# RSS_0_4.net
KiCad netlist of a schematic drawn in EAGLE
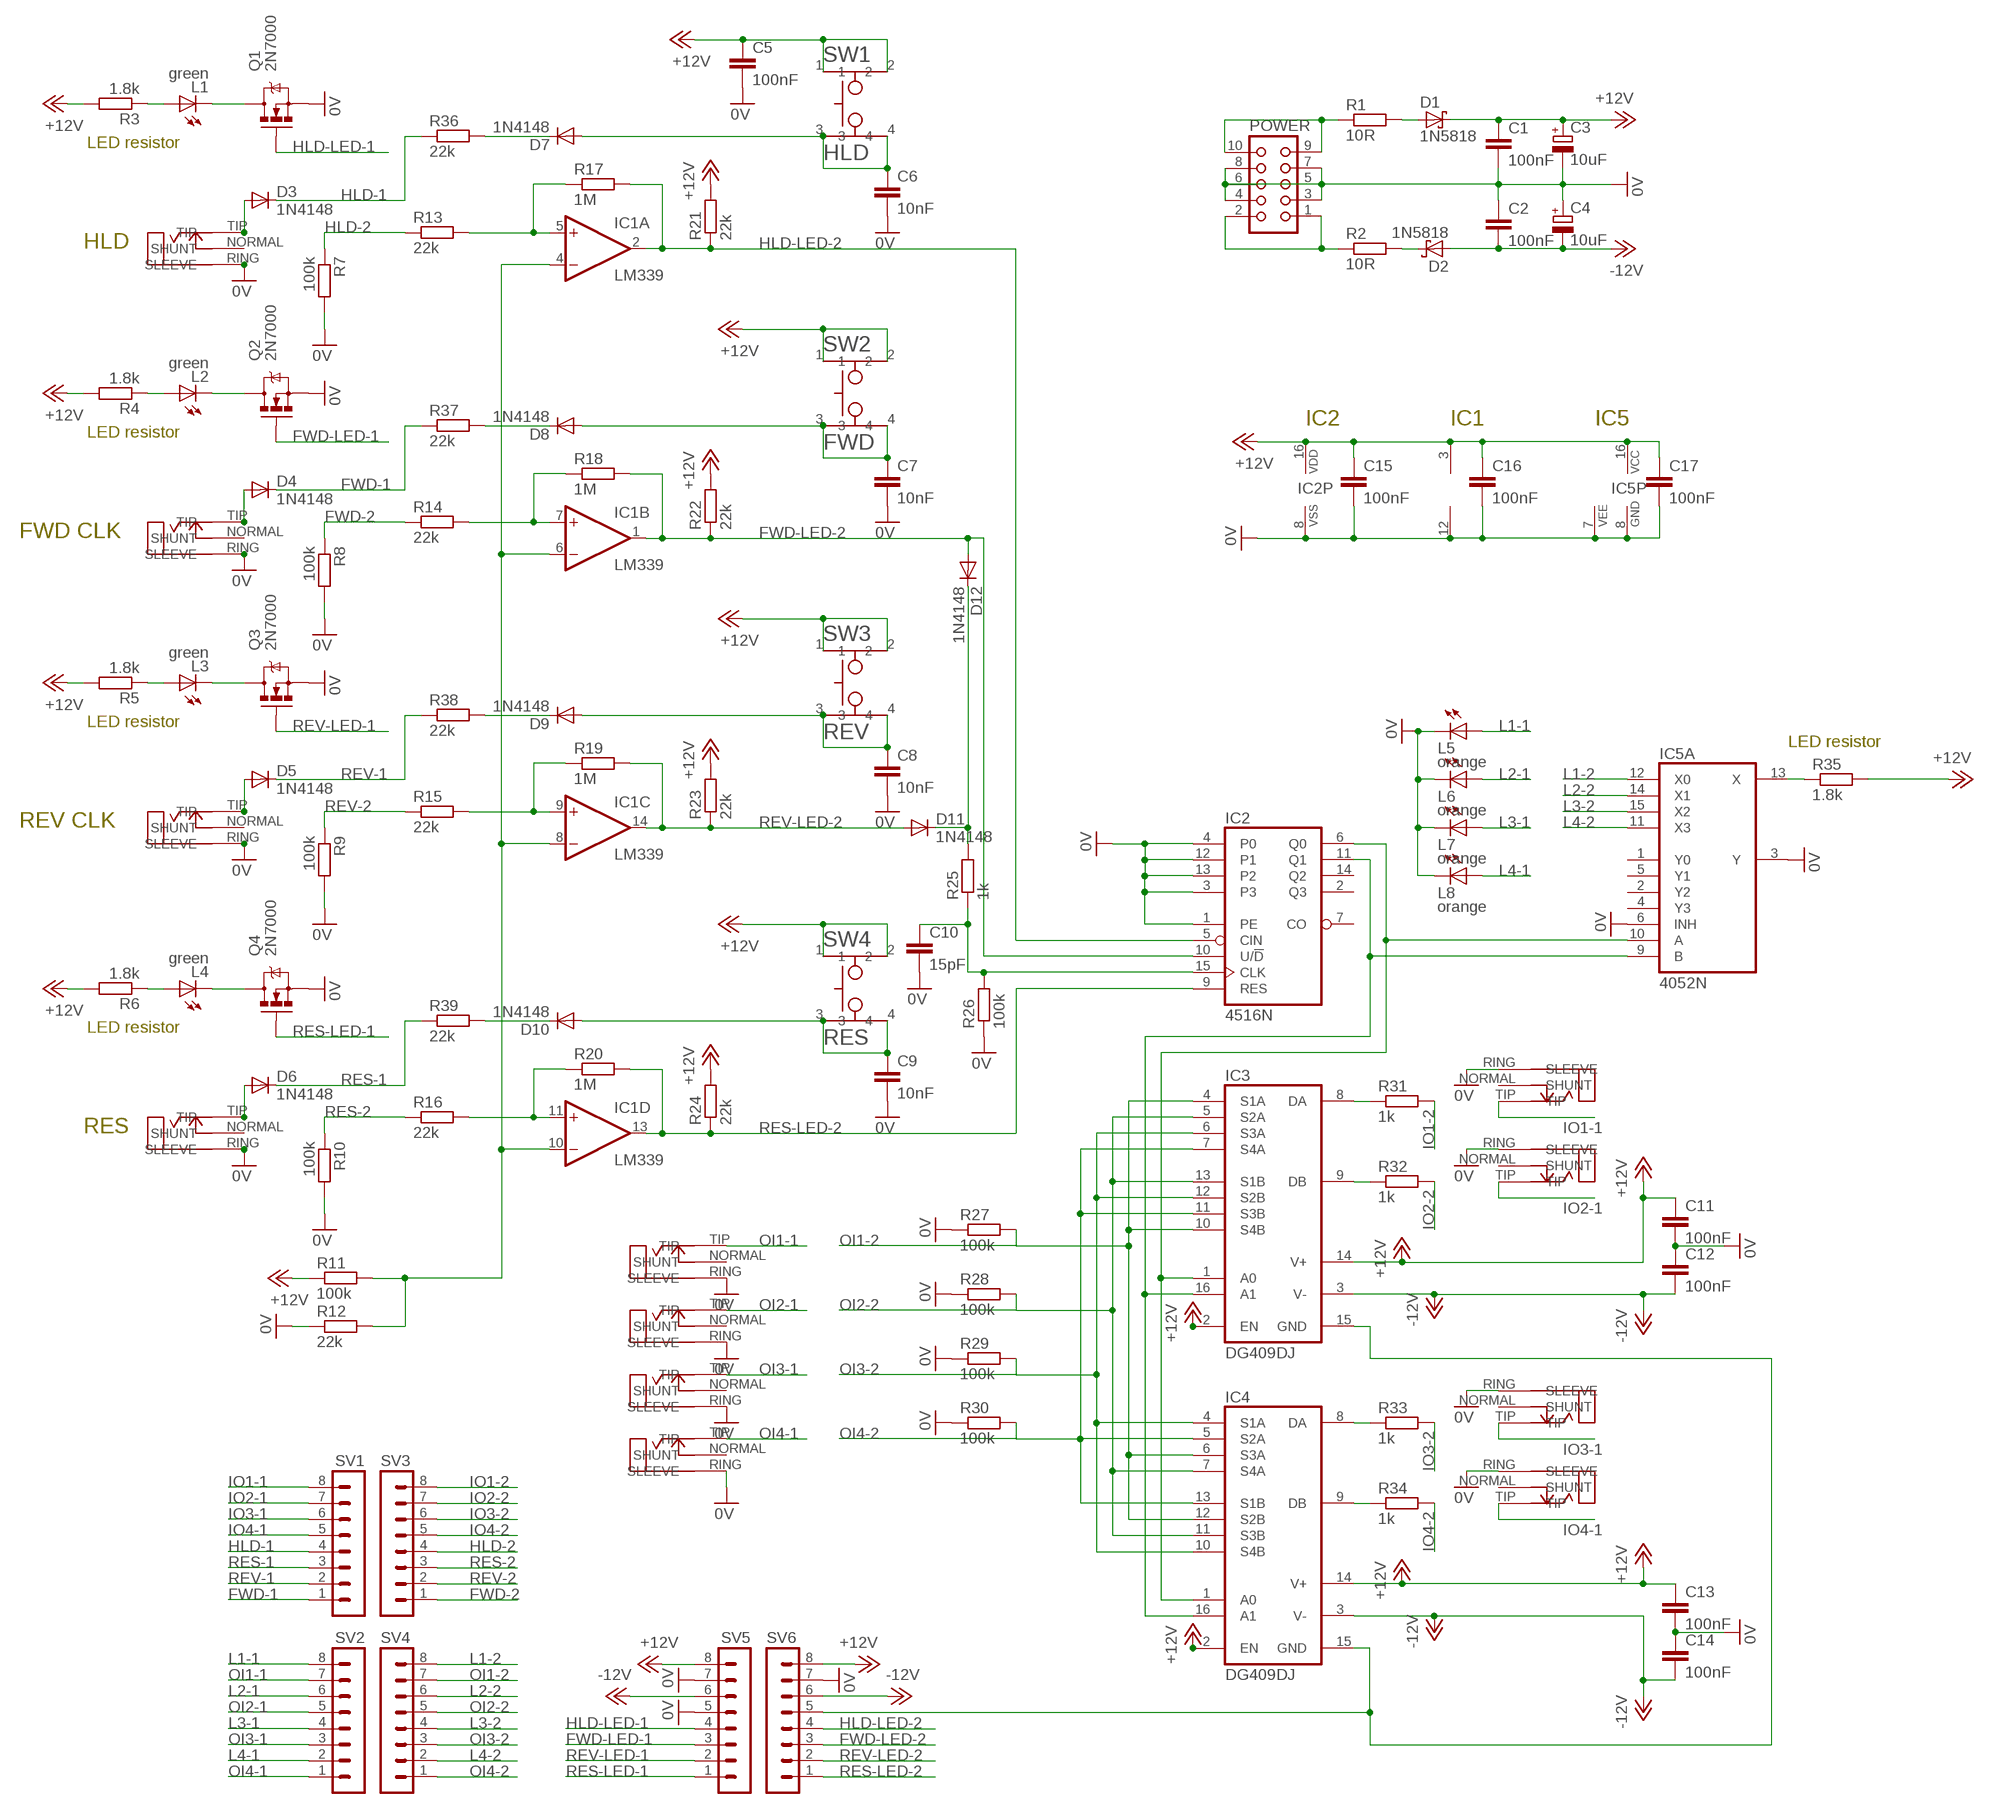
[diagram p0: schematic, sheet 1]

(export (version "E")
  (design (tool "Eeschema 10.0.6"))
  (components
    (comp (ref "C1")
      (value "100nF")
      (footprint "eagle-import:C025-024X044")
      (libsource (lib "eagle-import") (part "C-EU025-024X044"))
    )
    (comp (ref "C2")
      (value "100nF")
      (footprint "eagle-import:C025-024X044")
      (libsource (lib "eagle-import") (part "C-EU025-024X044"))
    )
    (comp (ref "C3")
      (value "10uF")
      (footprint "eagle-import:E2-5")
      (libsource (lib "eagle-import") (part "CPOL-EUE2-5"))
    )
    (comp (ref "C4")
      (value "10uF")
      (footprint "eagle-import:E2-5")
      (libsource (lib "eagle-import") (part "CPOL-EUE2-5"))
    )
    (comp (ref "C5")
      (value "100nF")
      (footprint "eagle-import:C025-024X044")
      (libsource (lib "eagle-import") (part "C-EU025-024X044"))
    )
    (comp (ref "C6")
      (value "10nF")
      (footprint "eagle-import:C025-024X044")
      (libsource (lib "eagle-import") (part "C-EU025-024X044"))
    )
    (comp (ref "C7")
      (value "10nF")
      (footprint "eagle-import:C025-024X044")
      (libsource (lib "eagle-import") (part "C-EU025-024X044"))
    )
    (comp (ref "C8")
      (value "10nF")
      (footprint "eagle-import:C025-024X044")
      (libsource (lib "eagle-import") (part "C-EU025-024X044"))
    )
    (comp (ref "C9")
      (value "10nF")
      (footprint "eagle-import:C025-024X044")
      (libsource (lib "eagle-import") (part "C-EU025-024X044"))
    )
    (comp (ref "C10")
      (value "15pF")
      (footprint "eagle-import:C025-024X044")
      (libsource (lib "eagle-import") (part "C-EU025-024X044"))
    )
    (comp (ref "C11")
      (value "100nF")
      (footprint "eagle-import:C025-024X044")
      (libsource (lib "eagle-import") (part "C-EU025-024X044"))
    )
    (comp (ref "C12")
      (value "100nF")
      (footprint "eagle-import:C025-024X044")
      (libsource (lib "eagle-import") (part "C-EU025-024X044"))
    )
    (comp (ref "C13")
      (value "100nF")
      (footprint "eagle-import:C025-024X044")
      (libsource (lib "eagle-import") (part "C-EU025-024X044"))
    )
    (comp (ref "C14")
      (value "100nF")
      (footprint "eagle-import:C025-024X044")
      (libsource (lib "eagle-import") (part "C-EU025-024X044"))
    )
    (comp (ref "C15")
      (value "100nF")
      (footprint "eagle-import:C025-024X044")
      (libsource (lib "eagle-import") (part "C-EU025-024X044"))
    )
    (comp (ref "C16")
      (value "100nF")
      (footprint "eagle-import:C025-024X044")
      (libsource (lib "eagle-import") (part "C-EU025-024X044"))
    )
    (comp (ref "C17")
      (value "100nF")
      (footprint "eagle-import:C025-024X044")
      (libsource (lib "eagle-import") (part "C-EU025-024X044"))
    )
    (comp (ref "D1")
      (value "1N5818")
      (footprint "eagle-import:DO41-7")
      (libsource (lib "eagle-import") (part "SB130DO-204AL"))
    )
    (comp (ref "D2")
      (value "1N5818")
      (footprint "eagle-import:DO41-7")
      (libsource (lib "eagle-import") (part "SB130DO-204AL"))
    )
    (comp (ref "D3")
      (value "1N4148")
      (footprint "eagle-import:DO35-7")
      (libsource (lib "eagle-import") (part "1N4148DO35-7"))
    )
    (comp (ref "D4")
      (value "1N4148")
      (footprint "eagle-import:DO35-7")
      (libsource (lib "eagle-import") (part "1N4148DO35-7"))
    )
    (comp (ref "D5")
      (value "1N4148")
      (footprint "eagle-import:DO35-7")
      (libsource (lib "eagle-import") (part "1N4148DO35-7"))
    )
    (comp (ref "D6")
      (value "1N4148")
      (footprint "eagle-import:DO35-7")
      (libsource (lib "eagle-import") (part "1N4148DO35-7"))
    )
    (comp (ref "D7")
      (value "1N4148")
      (footprint "eagle-import:DO35-7")
      (libsource (lib "eagle-import") (part "1N4148DO35-7"))
    )
    (comp (ref "D8")
      (value "1N4148")
      (footprint "eagle-import:DO35-7")
      (libsource (lib "eagle-import") (part "1N4148DO35-7"))
    )
    (comp (ref "D9")
      (value "1N4148")
      (footprint "eagle-import:DO35-7")
      (libsource (lib "eagle-import") (part "1N4148DO35-7"))
    )
    (comp (ref "D10")
      (value "1N4148")
      (footprint "eagle-import:DO35-7")
      (libsource (lib "eagle-import") (part "1N4148DO35-7"))
    )
    (comp (ref "D11")
      (value "1N4148")
      (footprint "eagle-import:DO35-7")
      (libsource (lib "eagle-import") (part "1N4148DO35-7"))
    )
    (comp (ref "D12")
      (value "1N4148")
      (footprint "eagle-import:DO35-7")
      (libsource (lib "eagle-import") (part "1N4148DO35-7"))
    )
    (comp (ref "FWD")
      (value "ERTHENVAR_3.5MM_JACK")
      (footprint "eagle-import:THONKICON")
      (libsource (lib "eagle-import") (part "ERTHENVAR_3.5MM_JACK"))
    )
    (comp (ref "HLD")
      (value "ERTHENVAR_3.5MM_JACK")
      (footprint "eagle-import:THONKICON")
      (libsource (lib "eagle-import") (part "ERTHENVAR_3.5MM_JACK"))
    )
    (comp (ref "I/O1")
      (value "ERTHENVAR_3.5MM_JACK")
      (footprint "eagle-import:THONKICON")
      (libsource (lib "eagle-import") (part "ERTHENVAR_3.5MM_JACK"))
    )
    (comp (ref "I/O2")
      (value "ERTHENVAR_3.5MM_JACK")
      (footprint "eagle-import:THONKICON")
      (libsource (lib "eagle-import") (part "ERTHENVAR_3.5MM_JACK"))
    )
    (comp (ref "I/O3")
      (value "ERTHENVAR_3.5MM_JACK")
      (footprint "eagle-import:THONKICON")
      (libsource (lib "eagle-import") (part "ERTHENVAR_3.5MM_JACK"))
    )
    (comp (ref "I/O4")
      (value "ERTHENVAR_3.5MM_JACK")
      (footprint "eagle-import:THONKICON")
      (libsource (lib "eagle-import") (part "ERTHENVAR_3.5MM_JACK"))
    )
    (comp (ref "IC1")
      (value "LM339")
      (footprint "eagle-import:DIL14")
      (libsource (lib "eagle-import") (part "LM2901N"))
    )
    (comp (ref "IC2")
      (value "4516N")
      (footprint "eagle-import:DIL16")
      (libsource (lib "eagle-import") (part "4516N"))
    )
    (comp (ref "IC3")
      (value "DG409DJ")
      (footprint "eagle-import:DIL16")
      (fields (field (name "MF") "INTERSIL"))
      (libsource (lib "eagle-import") (part "DG409DJ"))
    )
    (comp (ref "IC4")
      (value "DG409DJ")
      (footprint "eagle-import:DIL16")
      (fields (field (name "MF") "INTERSIL"))
      (libsource (lib "eagle-import") (part "DG409DJ"))
    )
    (comp (ref "IC5")
      (value "4052N")
      (footprint "eagle-import:DIL16")
      (libsource (lib "eagle-import") (part "4052N"))
    )
    (comp (ref "L1")
      (value "green")
      (footprint "eagle-import:LED3MM")
      (libsource (lib "eagle-import") (part "LED3MM"))
    )
    (comp (ref "L2")
      (value "green")
      (footprint "eagle-import:LED3MM")
      (libsource (lib "eagle-import") (part "LED3MM"))
    )
    (comp (ref "L3")
      (value "green")
      (footprint "eagle-import:LED3MM")
      (libsource (lib "eagle-import") (part "LED3MM"))
    )
    (comp (ref "L4")
      (value "green")
      (footprint "eagle-import:LED3MM")
      (libsource (lib "eagle-import") (part "LED3MM"))
    )
    (comp (ref "L5")
      (value "orange")
      (footprint "eagle-import:LED3MM")
      (libsource (lib "eagle-import") (part "LED3MM"))
    )
    (comp (ref "L6")
      (value "orange")
      (footprint "eagle-import:LED3MM")
      (libsource (lib "eagle-import") (part "LED3MM"))
    )
    (comp (ref "L7")
      (value "orange")
      (footprint "eagle-import:LED3MM")
      (libsource (lib "eagle-import") (part "LED3MM"))
    )
    (comp (ref "L8")
      (value "orange")
      (footprint "eagle-import:LED3MM")
      (libsource (lib "eagle-import") (part "LED3MM"))
    )
    (comp (ref "O/I1")
      (value "ERTHENVAR_3.5MM_JACK")
      (footprint "eagle-import:THONKICON")
      (libsource (lib "eagle-import") (part "ERTHENVAR_3.5MM_JACK"))
    )
    (comp (ref "O/I2")
      (value "ERTHENVAR_3.5MM_JACK")
      (footprint "eagle-import:THONKICON")
      (libsource (lib "eagle-import") (part "ERTHENVAR_3.5MM_JACK"))
    )
    (comp (ref "O/I3")
      (value "ERTHENVAR_3.5MM_JACK")
      (footprint "eagle-import:THONKICON")
      (libsource (lib "eagle-import") (part "ERTHENVAR_3.5MM_JACK"))
    )
    (comp (ref "O/I4")
      (value "ERTHENVAR_3.5MM_JACK")
      (footprint "eagle-import:THONKICON")
      (libsource (lib "eagle-import") (part "ERTHENVAR_3.5MM_JACK"))
    )
    (comp (ref "POWER")
      (value "CON10L")
      (footprint "eagle-import:CON10L")
      (libsource (lib "eagle-import") (part "CON10L"))
    )
    (comp (ref "Q1")
      (value "2N7000")
      (footprint "eagle-import:TO92-LINE")
      (libsource (lib "eagle-import") (part "MOSFET-NCHANNEL2N7000"))
    )
    (comp (ref "Q2")
      (value "2N7000")
      (footprint "eagle-import:TO92-LINE")
      (libsource (lib "eagle-import") (part "MOSFET-NCHANNEL2N7000"))
    )
    (comp (ref "Q3")
      (value "2N7000")
      (footprint "eagle-import:TO92-LINE")
      (libsource (lib "eagle-import") (part "MOSFET-NCHANNEL2N7000"))
    )
    (comp (ref "Q4")
      (value "2N7000")
      (footprint "eagle-import:TO92-LINE")
      (libsource (lib "eagle-import") (part "MOSFET-NCHANNEL2N7000"))
    )
    (comp (ref "R1")
      (value "10R")
      (footprint "eagle-import:0207_9")
      (libsource (lib "eagle-import") (part "R-EU_0207/10"))
    )
    (comp (ref "R2")
      (value "10R")
      (footprint "eagle-import:0207_9")
      (libsource (lib "eagle-import") (part "R-EU_0207/10"))
    )
    (comp (ref "R3")
      (value "1.8k")
      (footprint "eagle-import:0207_9")
      (libsource (lib "eagle-import") (part "R-EU_0207/10"))
    )
    (comp (ref "R4")
      (value "1.8k")
      (footprint "eagle-import:0207_9")
      (libsource (lib "eagle-import") (part "R-EU_0207/10"))
    )
    (comp (ref "R5")
      (value "1.8k")
      (footprint "eagle-import:0207_9")
      (libsource (lib "eagle-import") (part "R-EU_0207/10"))
    )
    (comp (ref "R6")
      (value "1.8k")
      (footprint "eagle-import:0207_9")
      (libsource (lib "eagle-import") (part "R-EU_0207/10"))
    )
    (comp (ref "R7")
      (value "100k")
      (footprint "eagle-import:0207_9")
      (libsource (lib "eagle-import") (part "R-EU_0207/10"))
    )
    (comp (ref "R8")
      (value "100k")
      (footprint "eagle-import:0207_9")
      (libsource (lib "eagle-import") (part "R-EU_0207/10"))
    )
    (comp (ref "R9")
      (value "100k")
      (footprint "eagle-import:0207_9")
      (libsource (lib "eagle-import") (part "R-EU_0207/10"))
    )
    (comp (ref "R10")
      (value "100k")
      (footprint "eagle-import:0207_9")
      (libsource (lib "eagle-import") (part "R-EU_0207/10"))
    )
    (comp (ref "R11")
      (value "100k")
      (footprint "eagle-import:0207_9")
      (libsource (lib "eagle-import") (part "R-EU_0207/10"))
    )
    (comp (ref "R12")
      (value "22k")
      (footprint "eagle-import:0207_9")
      (libsource (lib "eagle-import") (part "R-EU_0207/10"))
    )
    (comp (ref "R13")
      (value "22k")
      (footprint "eagle-import:0207_9")
      (libsource (lib "eagle-import") (part "R-EU_0207/10"))
    )
    (comp (ref "R14")
      (value "22k")
      (footprint "eagle-import:0207_9")
      (libsource (lib "eagle-import") (part "R-EU_0207/10"))
    )
    (comp (ref "R15")
      (value "22k")
      (footprint "eagle-import:0207_9")
      (libsource (lib "eagle-import") (part "R-EU_0207/10"))
    )
    (comp (ref "R16")
      (value "22k")
      (footprint "eagle-import:0207_9")
      (libsource (lib "eagle-import") (part "R-EU_0207/10"))
    )
    (comp (ref "R17")
      (value "1M")
      (footprint "eagle-import:0207_9")
      (libsource (lib "eagle-import") (part "R-EU_0207/10"))
    )
    (comp (ref "R18")
      (value "1M")
      (footprint "eagle-import:0207_9")
      (libsource (lib "eagle-import") (part "R-EU_0207/10"))
    )
    (comp (ref "R19")
      (value "1M")
      (footprint "eagle-import:0207_9")
      (libsource (lib "eagle-import") (part "R-EU_0207/10"))
    )
    (comp (ref "R20")
      (value "1M")
      (footprint "eagle-import:0207_9")
      (libsource (lib "eagle-import") (part "R-EU_0207/10"))
    )
    (comp (ref "R21")
      (value "22k")
      (footprint "eagle-import:0207_9")
      (libsource (lib "eagle-import") (part "R-EU_0207/10"))
    )
    (comp (ref "R22")
      (value "22k")
      (footprint "eagle-import:0207_9")
      (libsource (lib "eagle-import") (part "R-EU_0207/10"))
    )
    (comp (ref "R23")
      (value "22k")
      (footprint "eagle-import:0207_9")
      (libsource (lib "eagle-import") (part "R-EU_0207/10"))
    )
    (comp (ref "R24")
      (value "22k")
      (footprint "eagle-import:0207_9")
      (libsource (lib "eagle-import") (part "R-EU_0207/10"))
    )
    (comp (ref "R25")
      (value "1k")
      (footprint "eagle-import:0207_9")
      (libsource (lib "eagle-import") (part "R-EU_0207/10"))
    )
    (comp (ref "R26")
      (value "100k")
      (footprint "eagle-import:0207_9")
      (libsource (lib "eagle-import") (part "R-EU_0207/10"))
    )
    (comp (ref "R27")
      (value "100k")
      (footprint "eagle-import:0207_9")
      (libsource (lib "eagle-import") (part "R-EU_0207/10"))
    )
    (comp (ref "R28")
      (value "100k")
      (footprint "eagle-import:0207_9")
      (libsource (lib "eagle-import") (part "R-EU_0207/10"))
    )
    (comp (ref "R29")
      (value "100k")
      (footprint "eagle-import:0207_9")
      (libsource (lib "eagle-import") (part "R-EU_0207/10"))
    )
    (comp (ref "R30")
      (value "100k")
      (footprint "eagle-import:0207_9")
      (libsource (lib "eagle-import") (part "R-EU_0207/10"))
    )
    (comp (ref "R31")
      (value "1k")
      (footprint "eagle-import:0207_9")
      (libsource (lib "eagle-import") (part "R-EU_0207/10"))
    )
    (comp (ref "R32")
      (value "1k")
      (footprint "eagle-import:0207_9")
      (libsource (lib "eagle-import") (part "R-EU_0207/10"))
    )
    (comp (ref "R33")
      (value "1k")
      (footprint "eagle-import:0207_9")
      (libsource (lib "eagle-import") (part "R-EU_0207/10"))
    )
    (comp (ref "R34")
      (value "1k")
      (footprint "eagle-import:0207_9")
      (libsource (lib "eagle-import") (part "R-EU_0207/10"))
    )
    (comp (ref "R35")
      (value "1.8k")
      (footprint "eagle-import:0207_9")
      (libsource (lib "eagle-import") (part "R-EU_0207/10"))
    )
    (comp (ref "R36")
      (value "22k")
      (footprint "eagle-import:0207_9")
      (libsource (lib "eagle-import") (part "R-EU_0207/10"))
    )
    (comp (ref "R37")
      (value "22k")
      (footprint "eagle-import:0207_9")
      (libsource (lib "eagle-import") (part "R-EU_0207/10"))
    )
    (comp (ref "R38")
      (value "22k")
      (footprint "eagle-import:0207_9")
      (libsource (lib "eagle-import") (part "R-EU_0207/10"))
    )
    (comp (ref "R39")
      (value "22k")
      (footprint "eagle-import:0207_9")
      (libsource (lib "eagle-import") (part "R-EU_0207/10"))
    )
    (comp (ref "RES")
      (value "ERTHENVAR_3.5MM_JACK")
      (footprint "eagle-import:THONKICON")
      (libsource (lib "eagle-import") (part "ERTHENVAR_3.5MM_JACK"))
    )
    (comp (ref "REV")
      (value "ERTHENVAR_3.5MM_JACK")
      (footprint "eagle-import:THONKICON")
      (libsource (lib "eagle-import") (part "ERTHENVAR_3.5MM_JACK"))
    )
    (comp (ref "SV1")
      (value "MA08-1")
      (footprint "eagle-import:MA08-1")
      (libsource (lib "eagle-import") (part "MA08-1"))
    )
    (comp (ref "SV2")
      (value "MA08-1")
      (footprint "eagle-import:MA08-1")
      (libsource (lib "eagle-import") (part "MA08-1"))
    )
    (comp (ref "SV3")
      (value "MA08-1")
      (footprint "eagle-import:MA08-1")
      (libsource (lib "eagle-import") (part "MA08-1"))
    )
    (comp (ref "SV4")
      (value "MA08-1")
      (footprint "eagle-import:MA08-1")
      (libsource (lib "eagle-import") (part "MA08-1"))
    )
    (comp (ref "SV5")
      (value "MA08-1")
      (footprint "eagle-import:MA08-1")
      (libsource (lib "eagle-import") (part "MA08-1"))
    )
    (comp (ref "SV6")
      (value "MA08-1")
      (footprint "eagle-import:MA08-1")
      (libsource (lib "eagle-import") (part "MA08-1"))
    )
    (comp (ref "SW1")
      (value "HLD")
      (footprint "eagle-import:TACTILE_ALPS")
      (libsource (lib "eagle-import") (part "TACTILE_ALPS"))
    )
    (comp (ref "SW2")
      (value "FWD")
      (footprint "eagle-import:TACTILE_ALPS")
      (libsource (lib "eagle-import") (part "TACTILE_ALPS"))
    )
    (comp (ref "SW3")
      (value "REV")
      (footprint "eagle-import:TACTILE_ALPS")
      (libsource (lib "eagle-import") (part "TACTILE_ALPS"))
    )
    (comp (ref "SW4")
      (value "RES")
      (footprint "eagle-import:TACTILE_ALPS")
      (libsource (lib "eagle-import") (part "TACTILE_ALPS"))
    )
  )
  (nets
    (net (code "1") (name "+12V") (class "Default")
      (node (ref "C1") (pin "1") (pinfunction "1_1") (pintype "passive"))
      (node (ref "C11") (pin "1") (pinfunction "1_1") (pintype "passive"))
      (node (ref "C13") (pin "1") (pinfunction "1_1") (pintype "passive"))
      (node (ref "C15") (pin "1") (pinfunction "1_1") (pintype "passive"))
      (node (ref "C16") (pin "1") (pinfunction "1_1") (pintype "passive"))
      (node (ref "C17") (pin "1") (pinfunction "1_1") (pintype "passive"))
      (node (ref "C3") (pin "+") (pinfunction "+_+") (pintype "passive"))
      (node (ref "C5") (pin "1") (pinfunction "1_1") (pintype "passive"))
      (node (ref "D1") (pin "C") (pinfunction "C_C") (pintype "passive"))
      (node (ref "IC1") (pin "3") (pinfunction "V+_3") (pintype "power_in"))
      (node (ref "IC2") (pin "16") (pinfunction "VDD_16") (pintype "power_in"))
      (node (ref "IC3") (pin "14") (pinfunction "V+_14") (pintype "power_in"))
      (node (ref "IC3") (pin "2") (pinfunction "EN_2") (pintype "input"))
      (node (ref "IC4") (pin "14") (pinfunction "V+_14") (pintype "power_in"))
      (node (ref "IC4") (pin "2") (pinfunction "EN_2") (pintype "input"))
      (node (ref "IC5") (pin "16") (pinfunction "VCC_16") (pintype "power_in"))
      (node (ref "R11") (pin "1") (pinfunction "1_1") (pintype "passive"))
      (node (ref "R21") (pin "2") (pinfunction "2_2") (pintype "passive"))
      (node (ref "R22") (pin "2") (pinfunction "2_2") (pintype "passive"))
      (node (ref "R23") (pin "2") (pinfunction "2_2") (pintype "passive"))
      (node (ref "R24") (pin "2") (pinfunction "2_2") (pintype "passive"))
      (node (ref "R3") (pin "2") (pinfunction "2_2") (pintype "passive"))
      (node (ref "R35") (pin "2") (pinfunction "2_2") (pintype "passive"))
      (node (ref "R4") (pin "2") (pinfunction "2_2") (pintype "passive"))
      (node (ref "R5") (pin "2") (pinfunction "2_2") (pintype "passive"))
      (node (ref "R6") (pin "2") (pinfunction "2_2") (pintype "passive"))
      (node (ref "SV5") (pin "8") (pinfunction "8_8") (pintype "passive"))
      (node (ref "SV6") (pin "8") (pinfunction "8_8") (pintype "passive"))
      (node (ref "SW1") (pin "1") (pinfunction "1_1") (pintype "bidirectional"))
      (node (ref "SW1") (pin "2") (pinfunction "2_2") (pintype "bidirectional"))
      (node (ref "SW2") (pin "1") (pinfunction "1_1") (pintype "bidirectional"))
      (node (ref "SW2") (pin "2") (pinfunction "2_2") (pintype "bidirectional"))
      (node (ref "SW3") (pin "1") (pinfunction "1_1") (pintype "bidirectional"))
      (node (ref "SW3") (pin "2") (pinfunction "2_2") (pintype "bidirectional"))
      (node (ref "SW4") (pin "1") (pinfunction "1_1") (pintype "bidirectional"))
      (node (ref "SW4") (pin "2") (pinfunction "2_2") (pintype "bidirectional"))
    )
    (net (code "2") (name "-12V") (class "Default")
      (node (ref "C12") (pin "2") (pinfunction "2_2") (pintype "passive"))
      (node (ref "C14") (pin "2") (pinfunction "2_2") (pintype "passive"))
      (node (ref "C2") (pin "2") (pinfunction "2_2") (pintype "passive"))
      (node (ref "C4") (pin "-") (pinfunction "-_-") (pintype "passive"))
      (node (ref "D2") (pin "A") (pinfunction "A_A") (pintype "passive"))
      (node (ref "IC3") (pin "3") (pinfunction "V-_3") (pintype "power_in"))
      (node (ref "IC4") (pin "3") (pinfunction "V-_3") (pintype "power_in"))
      (node (ref "SV5") (pin "6") (pinfunction "6_6") (pintype "passive"))
      (node (ref "SV6") (pin "6") (pinfunction "6_6") (pintype "passive"))
    )
    (net (code "3") (name "/FWD-1") (class "Default")
      (node (ref "D4") (pin "C") (pinfunction "C_C") (pintype "passive"))
      (node (ref "R37") (pin "1") (pinfunction "1_1") (pintype "passive"))
      (node (ref "SV1") (pin "1") (pinfunction "1_1") (pintype "passive"))
    )
    (net (code "4") (name "/FWD-2") (class "Default")
      (node (ref "R14") (pin "1") (pinfunction "1_1") (pintype "passive"))
      (node (ref "R8") (pin "1") (pinfunction "1_1") (pintype "passive"))
      (node (ref "SV3") (pin "1") (pinfunction "1_1") (pintype "passive"))
    )
    (net (code "5") (name "/FWD-LED-1") (class "Default")
      (node (ref "Q2") (pin "2") (pinfunction "G_2") (pintype "passive"))
      (node (ref "SV5") (pin "3") (pinfunction "3_3") (pintype "passive"))
    )
    (net (code "6") (name "/FWD-LED-2") (class "Default")
      (node (ref "D12") (pin "A") (pinfunction "A_A") (pintype "passive"))
      (node (ref "IC1") (pin "1") (pinfunction "OUT_1") (pintype "output"))
      (node (ref "IC2") (pin "10") (pinfunction "U/~{D}_10") (pintype "input"))
      (node (ref "R18") (pin "2") (pinfunction "2_2") (pintype "passive"))
      (node (ref "R22") (pin "1") (pinfunction "1_1") (pintype "passive"))
      (node (ref "SV6") (pin "3") (pinfunction "3_3") (pintype "passive"))
    )
    (net (code "7") (name "/HLD-1") (class "Default")
      (node (ref "D3") (pin "C") (pinfunction "C_C") (pintype "passive"))
      (node (ref "R36") (pin "1") (pinfunction "1_1") (pintype "passive"))
      (node (ref "SV1") (pin "4") (pinfunction "4_4") (pintype "passive"))
    )
    (net (code "8") (name "/HLD-2") (class "Default")
      (node (ref "R13") (pin "1") (pinfunction "1_1") (pintype "passive"))
      (node (ref "R7") (pin "1") (pinfunction "1_1") (pintype "passive"))
      (node (ref "SV3") (pin "4") (pinfunction "4_4") (pintype "passive"))
    )
    (net (code "9") (name "/HLD-LED-1") (class "Default")
      (node (ref "Q1") (pin "2") (pinfunction "G_2") (pintype "passive"))
      (node (ref "SV5") (pin "4") (pinfunction "4_4") (pintype "passive"))
    )
    (net (code "10") (name "/HLD-LED-2") (class "Default")
      (node (ref "IC1") (pin "2") (pinfunction "OUT_2") (pintype "output"))
      (node (ref "IC2") (pin "5") (pinfunction "CIN_5") (pintype "input"))
      (node (ref "R17") (pin "2") (pinfunction "2_2") (pintype "passive"))
      (node (ref "R21") (pin "1") (pinfunction "1_1") (pintype "passive"))
      (node (ref "SV6") (pin "4") (pinfunction "4_4") (pintype "passive"))
    )
    (net (code "11") (name "/IO1-1") (class "Default")
      (node (ref "I/O1") (pin "TIP") (pinfunction "TIP_TIP") (pintype "bidirectional"))
      (node (ref "SV1") (pin "8") (pinfunction "8_8") (pintype "passive"))
    )
    (net (code "12") (name "/IO1-2") (class "Default")
      (node (ref "R31") (pin "2") (pinfunction "2_2") (pintype "passive"))
      (node (ref "SV3") (pin "8") (pinfunction "8_8") (pintype "passive"))
    )
    (net (code "13") (name "/IO2-1") (class "Default")
      (node (ref "I/O2") (pin "TIP") (pinfunction "TIP_TIP") (pintype "bidirectional"))
      (node (ref "SV1") (pin "7") (pinfunction "7_7") (pintype "passive"))
    )
    (net (code "14") (name "/IO2-2") (class "Default")
      (node (ref "R32") (pin "2") (pinfunction "2_2") (pintype "passive"))
      (node (ref "SV3") (pin "7") (pinfunction "7_7") (pintype "passive"))
    )
    (net (code "15") (name "/IO3-1") (class "Default")
      (node (ref "I/O3") (pin "TIP") (pinfunction "TIP_TIP") (pintype "bidirectional"))
      (node (ref "SV1") (pin "6") (pinfunction "6_6") (pintype "passive"))
    )
    (net (code "16") (name "/IO3-2") (class "Default")
      (node (ref "R33") (pin "2") (pinfunction "2_2") (pintype "passive"))
      (node (ref "SV3") (pin "6") (pinfunction "6_6") (pintype "passive"))
    )
    (net (code "17") (name "/IO4-1") (class "Default")
      (node (ref "I/O4") (pin "TIP") (pinfunction "TIP_TIP") (pintype "bidirectional"))
      (node (ref "SV1") (pin "5") (pinfunction "5_5") (pintype "passive"))
    )
    (net (code "18") (name "/IO4-2") (class "Default")
      (node (ref "R34") (pin "2") (pinfunction "2_2") (pintype "passive"))
      (node (ref "SV3") (pin "5") (pinfunction "5_5") (pintype "passive"))
    )
    (net (code "19") (name "/L1-1") (class "Default")
      (node (ref "L5") (pin "A") (pinfunction "A_A") (pintype "passive"))
      (node (ref "SV2") (pin "8") (pinfunction "8_8") (pintype "passive"))
    )
    (net (code "20") (name "/L1-2") (class "Default")
      (node (ref "IC5") (pin "12") (pinfunction "X0_12") (pintype "bidirectional"))
      (node (ref "SV4") (pin "8") (pinfunction "8_8") (pintype "passive"))
    )
    (net (code "21") (name "/L2-1") (class "Default")
      (node (ref "L6") (pin "A") (pinfunction "A_A") (pintype "passive"))
      (node (ref "SV2") (pin "6") (pinfunction "6_6") (pintype "passive"))
    )
    (net (code "22") (name "/L2-2") (class "Default")
      (node (ref "IC5") (pin "14") (pinfunction "X1_14") (pintype "bidirectional"))
      (node (ref "SV4") (pin "6") (pinfunction "6_6") (pintype "passive"))
    )
    (net (code "23") (name "/L3-1") (class "Default")
      (node (ref "L7") (pin "A") (pinfunction "A_A") (pintype "passive"))
      (node (ref "SV2") (pin "4") (pinfunction "4_4") (pintype "passive"))
    )
    (net (code "24") (name "/L3-2") (class "Default")
      (node (ref "IC5") (pin "15") (pinfunction "X2_15") (pintype "bidirectional"))
      (node (ref "SV4") (pin "4") (pinfunction "4_4") (pintype "passive"))
    )
    (net (code "25") (name "/L4-1") (class "Default")
      (node (ref "L8") (pin "A") (pinfunction "A_A") (pintype "passive"))
      (node (ref "SV2") (pin "2") (pinfunction "2_2") (pintype "passive"))
    )
    (net (code "26") (name "/L4-2") (class "Default")
      (node (ref "IC5") (pin "11") (pinfunction "X3_11") (pintype "bidirectional"))
      (node (ref "SV4") (pin "2") (pinfunction "2_2") (pintype "passive"))
    )
    (net (code "27") (name "/OI1-1") (class "Default")
      (node (ref "O/I1") (pin "TIP") (pinfunction "TIP_TIP") (pintype "bidirectional"))
      (node (ref "SV2") (pin "7") (pinfunction "7_7") (pintype "passive"))
    )
    (net (code "28") (name "/OI1-2") (class "Default")
      (node (ref "IC3") (pin "10") (pinfunction "S4B_10") (pintype "passive"))
      (node (ref "IC3") (pin "4") (pinfunction "S1A_4") (pintype "passive"))
      (node (ref "IC4") (pin "12") (pinfunction "S2B_12") (pintype "passive"))
      (node (ref "IC4") (pin "6") (pinfunction "S3A_6") (pintype "passive"))
      (node (ref "R27") (pin "2") (pinfunction "2_2") (pintype "passive"))
      (node (ref "SV4") (pin "7") (pinfunction "7_7") (pintype "passive"))
    )
    (net (code "29") (name "/OI2-1") (class "Default")
      (node (ref "O/I2") (pin "TIP") (pinfunction "TIP_TIP") (pintype "bidirectional"))
      (node (ref "SV2") (pin "5") (pinfunction "5_5") (pintype "passive"))
    )
    (net (code "30") (name "/OI2-2") (class "Default")
      (node (ref "IC3") (pin "13") (pinfunction "S1B_13") (pintype "passive"))
      (node (ref "IC3") (pin "5") (pinfunction "S2A_5") (pintype "passive"))
      (node (ref "IC4") (pin "11") (pinfunction "S3B_11") (pintype "passive"))
      (node (ref "IC4") (pin "7") (pinfunction "S4A_7") (pintype "passive"))
      (node (ref "R28") (pin "2") (pinfunction "2_2") (pintype "passive"))
      (node (ref "SV4") (pin "5") (pinfunction "5_5") (pintype "passive"))
    )
    (net (code "31") (name "/OI3-1") (class "Default")
      (node (ref "O/I3") (pin "TIP") (pinfunction "TIP_TIP") (pintype "bidirectional"))
      (node (ref "SV2") (pin "3") (pinfunction "3_3") (pintype "passive"))
    )
    (net (code "32") (name "/OI3-2") (class "Default")
      (node (ref "IC3") (pin "12") (pinfunction "S2B_12") (pintype "passive"))
      (node (ref "IC3") (pin "6") (pinfunction "S3A_6") (pintype "passive"))
      (node (ref "IC4") (pin "10") (pinfunction "S4B_10") (pintype "passive"))
      (node (ref "IC4") (pin "4") (pinfunction "S1A_4") (pintype "passive"))
      (node (ref "R29") (pin "2") (pinfunction "2_2") (pintype "passive"))
      (node (ref "SV4") (pin "3") (pinfunction "3_3") (pintype "passive"))
    )
    (net (code "33") (name "/OI4-1") (class "Default")
      (node (ref "O/I4") (pin "TIP") (pinfunction "TIP_TIP") (pintype "bidirectional"))
      (node (ref "SV2") (pin "1") (pinfunction "1_1") (pintype "passive"))
    )
    (net (code "34") (name "/OI4-2") (class "Default")
      (node (ref "IC3") (pin "11") (pinfunction "S3B_11") (pintype "passive"))
      (node (ref "IC3") (pin "7") (pinfunction "S4A_7") (pintype "passive"))
      (node (ref "IC4") (pin "13") (pinfunction "S1B_13") (pintype "passive"))
      (node (ref "IC4") (pin "5") (pinfunction "S2A_5") (pintype "passive"))
      (node (ref "R30") (pin "2") (pinfunction "2_2") (pintype "passive"))
      (node (ref "SV4") (pin "1") (pinfunction "1_1") (pintype "passive"))
    )
    (net (code "35") (name "/RES-1") (class "Default")
      (node (ref "D6") (pin "C") (pinfunction "C_C") (pintype "passive"))
      (node (ref "R39") (pin "1") (pinfunction "1_1") (pintype "passive"))
      (node (ref "SV1") (pin "3") (pinfunction "3_3") (pintype "passive"))
    )
    (net (code "36") (name "/RES-2") (class "Default")
      (node (ref "R10") (pin "1") (pinfunction "1_1") (pintype "passive"))
      (node (ref "R16") (pin "1") (pinfunction "1_1") (pintype "passive"))
      (node (ref "SV3") (pin "3") (pinfunction "3_3") (pintype "passive"))
    )
    (net (code "37") (name "/RES-LED-1") (class "Default")
      (node (ref "Q4") (pin "2") (pinfunction "G_2") (pintype "passive"))
      (node (ref "SV5") (pin "1") (pinfunction "1_1") (pintype "passive"))
    )
    (net (code "38") (name "/RES-LED-2") (class "Default")
      (node (ref "IC1") (pin "13") (pinfunction "OUT_13") (pintype "output"))
      (node (ref "IC2") (pin "9") (pinfunction "RES_9") (pintype "input"))
      (node (ref "R20") (pin "2") (pinfunction "2_2") (pintype "passive"))
      (node (ref "R24") (pin "1") (pinfunction "1_1") (pintype "passive"))
      (node (ref "SV6") (pin "1") (pinfunction "1_1") (pintype "passive"))
    )
    (net (code "39") (name "/REV-1") (class "Default")
      (node (ref "D5") (pin "C") (pinfunction "C_C") (pintype "passive"))
      (node (ref "R38") (pin "1") (pinfunction "1_1") (pintype "passive"))
      (node (ref "SV1") (pin "2") (pinfunction "2_2") (pintype "passive"))
    )
    (net (code "40") (name "/REV-2") (class "Default")
      (node (ref "R15") (pin "1") (pinfunction "1_1") (pintype "passive"))
      (node (ref "R9") (pin "1") (pinfunction "1_1") (pintype "passive"))
      (node (ref "SV3") (pin "2") (pinfunction "2_2") (pintype "passive"))
    )
    (net (code "41") (name "/REV-LED-1") (class "Default")
      (node (ref "Q3") (pin "2") (pinfunction "G_2") (pintype "passive"))
      (node (ref "SV5") (pin "2") (pinfunction "2_2") (pintype "passive"))
    )
    (net (code "42") (name "/REV-LED-2") (class "Default")
      (node (ref "D11") (pin "A") (pinfunction "A_A") (pintype "passive"))
      (node (ref "IC1") (pin "14") (pinfunction "OUT_14") (pintype "output"))
      (node (ref "R19") (pin "2") (pinfunction "2_2") (pintype "passive"))
      (node (ref "R23") (pin "1") (pinfunction "1_1") (pintype "passive"))
      (node (ref "SV6") (pin "2") (pinfunction "2_2") (pintype "passive"))
    )
    (net (code "43") (name "0V") (class "Default")
      (node (ref "C1") (pin "2") (pinfunction "2_2") (pintype "passive"))
      (node (ref "C10") (pin "2") (pinfunction "2_2") (pintype "passive"))
      (node (ref "C11") (pin "2") (pinfunction "2_2") (pintype "passive"))
      (node (ref "C12") (pin "1") (pinfunction "1_1") (pintype "passive"))
      (node (ref "C13") (pin "2") (pinfunction "2_2") (pintype "passive"))
      (node (ref "C14") (pin "1") (pinfunction "1_1") (pintype "passive"))
      (node (ref "C15") (pin "2") (pinfunction "2_2") (pintype "passive"))
      (node (ref "C16") (pin "2") (pinfunction "2_2") (pintype "passive"))
      (node (ref "C17") (pin "2") (pinfunction "2_2") (pintype "passive"))
      (node (ref "C2") (pin "1") (pinfunction "1_1") (pintype "passive"))
      (node (ref "C3") (pin "-") (pinfunction "-_-") (pintype "passive"))
      (node (ref "C4") (pin "+") (pinfunction "+_+") (pintype "passive"))
      (node (ref "C5") (pin "2") (pinfunction "2_2") (pintype "passive"))
      (node (ref "C6") (pin "2") (pinfunction "2_2") (pintype "passive"))
      (node (ref "C7") (pin "2") (pinfunction "2_2") (pintype "passive"))
      (node (ref "C8") (pin "2") (pinfunction "2_2") (pintype "passive"))
      (node (ref "C9") (pin "2") (pinfunction "2_2") (pintype "passive"))
      (node (ref "FWD") (pin "RING") (pinfunction "SLEEVE_RING") (pintype "bidirectional"))
      (node (ref "HLD") (pin "RING") (pinfunction "SLEEVE_RING") (pintype "bidirectional"))
      (node (ref "I/O1") (pin "RING") (pinfunction "SLEEVE_RING") (pintype "bidirectional"))
      (node (ref "I/O2") (pin "RING") (pinfunction "SLEEVE_RING") (pintype "bidirectional"))
      (node (ref "I/O3") (pin "RING") (pinfunction "SLEEVE_RING") (pintype "bidirectional"))
      (node (ref "I/O4") (pin "RING") (pinfunction "SLEEVE_RING") (pintype "bidirectional"))
      (node (ref "IC1") (pin "12") (pinfunction "V-_12") (pintype "power_in"))
      (node (ref "IC2") (pin "1") (pinfunction "PE_1") (pintype "input"))
      (node (ref "IC2") (pin "12") (pinfunction "P1_12") (pintype "input"))
      (node (ref "IC2") (pin "13") (pinfunction "P2_13") (pintype "input"))
      (node (ref "IC2") (pin "3") (pinfunction "P3_3") (pintype "input"))
      (node (ref "IC2") (pin "4") (pinfunction "P0_4") (pintype "input"))
      (node (ref "IC2") (pin "8") (pinfunction "VSS_8") (pintype "power_in"))
      (node (ref "IC5") (pin "3") (pinfunction "Y_3") (pintype "bidirectional"))
      (node (ref "IC5") (pin "6") (pinfunction "INH_6") (pintype "input"))
      (node (ref "IC5") (pin "7") (pinfunction "VEE_7") (pintype "power_in"))
      (node (ref "IC5") (pin "8") (pinfunction "GND_8") (pintype "power_in"))
      (node (ref "L5") (pin "K") (pinfunction "C_K") (pintype "passive"))
      (node (ref "L6") (pin "K") (pinfunction "C_K") (pintype "passive"))
      (node (ref "L7") (pin "K") (pinfunction "C_K") (pintype "passive"))
      (node (ref "L8") (pin "K") (pinfunction "C_K") (pintype "passive"))
      (node (ref "O/I1") (pin "RING") (pinfunction "SLEEVE_RING") (pintype "bidirectional"))
      (node (ref "O/I2") (pin "RING") (pinfunction "SLEEVE_RING") (pintype "bidirectional"))
      (node (ref "O/I3") (pin "RING") (pinfunction "SLEEVE_RING") (pintype "bidirectional"))
      (node (ref "O/I4") (pin "RING") (pinfunction "SLEEVE_RING") (pintype "bidirectional"))
      (node (ref "POWER") (pin "3") (pinfunction "3_3") (pintype "passive"))
      (node (ref "POWER") (pin "4") (pinfunction "4_4") (pintype "passive"))
      (node (ref "POWER") (pin "5") (pinfunction "5_5") (pintype "passive"))
      (node (ref "POWER") (pin "6") (pinfunction "6_6") (pintype "passive"))
      (node (ref "POWER") (pin "7") (pinfunction "7_7") (pintype "passive"))
      (node (ref "POWER") (pin "8") (pinfunction "8_8") (pintype "passive"))
      (node (ref "Q1") (pin "3") (pinfunction "S_3") (pintype "passive"))
      (node (ref "Q2") (pin "3") (pinfunction "S_3") (pintype "passive"))
      (node (ref "Q3") (pin "3") (pinfunction "S_3") (pintype "passive"))
      (node (ref "Q4") (pin "3") (pinfunction "S_3") (pintype "passive"))
      (node (ref "R10") (pin "2") (pinfunction "2_2") (pintype "passive"))
      (node (ref "R12") (pin "1") (pinfunction "1_1") (pintype "passive"))
      (node (ref "R26") (pin "1") (pinfunction "1_1") (pintype "passive"))
      (node (ref "R27") (pin "1") (pinfunction "1_1") (pintype "passive"))
      (node (ref "R28") (pin "1") (pinfunction "1_1") (pintype "passive"))
      (node (ref "R29") (pin "1") (pinfunction "1_1") (pintype "passive"))
      (node (ref "R30") (pin "1") (pinfunction "1_1") (pintype "passive"))
      (node (ref "R7") (pin "2") (pinfunction "2_2") (pintype "passive"))
      (node (ref "R8") (pin "2") (pinfunction "2_2") (pintype "passive"))
      (node (ref "R9") (pin "2") (pinfunction "2_2") (pintype "passive"))
      (node (ref "RES") (pin "RING") (pinfunction "SLEEVE_RING") (pintype "bidirectional"))
      (node (ref "REV") (pin "RING") (pinfunction "SLEEVE_RING") (pintype "bidirectional"))
      (node (ref "SV5") (pin "5") (pinfunction "5_5") (pintype "passive"))
      (node (ref "SV5") (pin "7") (pinfunction "7_7") (pintype "passive"))
      (node (ref "SV6") (pin "7") (pinfunction "7_7") (pintype "passive"))
    )
    (net (code "44") (name "Net-(C6-Pad1)") (class "Default")
      (node (ref "C6") (pin "1") (pinfunction "1_1") (pintype "passive"))
      (node (ref "D7") (pin "A") (pinfunction "A_A") (pintype "passive"))
      (node (ref "SW1") (pin "3") (pinfunction "3_3") (pintype "bidirectional"))
      (node (ref "SW1") (pin "4") (pinfunction "4_4") (pintype "bidirectional"))
    )
    (net (code "45") (name "Net-(C7-Pad1)") (class "Default")
      (node (ref "C7") (pin "1") (pinfunction "1_1") (pintype "passive"))
      (node (ref "D8") (pin "A") (pinfunction "A_A") (pintype "passive"))
      (node (ref "SW2") (pin "3") (pinfunction "3_3") (pintype "bidirectional"))
      (node (ref "SW2") (pin "4") (pinfunction "4_4") (pintype "bidirectional"))
    )
    (net (code "46") (name "Net-(C8-Pad1)") (class "Default")
      (node (ref "C8") (pin "1") (pinfunction "1_1") (pintype "passive"))
      (node (ref "D9") (pin "A") (pinfunction "A_A") (pintype "passive"))
      (node (ref "SW3") (pin "3") (pinfunction "3_3") (pintype "bidirectional"))
      (node (ref "SW3") (pin "4") (pinfunction "4_4") (pintype "bidirectional"))
    )
    (net (code "47") (name "Net-(C9-Pad1)") (class "Default")
      (node (ref "C9") (pin "1") (pinfunction "1_1") (pintype "passive"))
      (node (ref "D10") (pin "A") (pinfunction "A_A") (pintype "passive"))
      (node (ref "SW4") (pin "3") (pinfunction "3_3") (pintype "bidirectional"))
      (node (ref "SW4") (pin "4") (pinfunction "4_4") (pintype "bidirectional"))
    )
    (net (code "48") (name "Net-(D1-PadA)") (class "Default")
      (node (ref "D1") (pin "A") (pinfunction "A_A") (pintype "passive"))
      (node (ref "R1") (pin "2") (pinfunction "2_2") (pintype "passive"))
    )
    (net (code "49") (name "Net-(D2-PadC)") (class "Default")
      (node (ref "D2") (pin "C") (pinfunction "C_C") (pintype "passive"))
      (node (ref "R2") (pin "2") (pinfunction "2_2") (pintype "passive"))
    )
    (net (code "50") (name "Net-(D3-PadA)") (class "Default")
      (node (ref "D3") (pin "A") (pinfunction "A_A") (pintype "passive"))
      (node (ref "HLD") (pin "TIP") (pinfunction "TIP_TIP") (pintype "bidirectional"))
    )
    (net (code "51") (name "Net-(D4-PadA)") (class "Default")
      (node (ref "D4") (pin "A") (pinfunction "A_A") (pintype "passive"))
      (node (ref "FWD") (pin "TIP") (pinfunction "TIP_TIP") (pintype "bidirectional"))
    )
    (net (code "52") (name "Net-(D5-PadA)") (class "Default")
      (node (ref "D5") (pin "A") (pinfunction "A_A") (pintype "passive"))
      (node (ref "REV") (pin "TIP") (pinfunction "TIP_TIP") (pintype "bidirectional"))
    )
    (net (code "53") (name "Net-(D6-PadA)") (class "Default")
      (node (ref "D6") (pin "A") (pinfunction "A_A") (pintype "passive"))
      (node (ref "RES") (pin "TIP") (pinfunction "TIP_TIP") (pintype "bidirectional"))
    )
    (net (code "54") (name "Net-(D7-PadC)") (class "Default")
      (node (ref "D7") (pin "C") (pinfunction "C_C") (pintype "passive"))
      (node (ref "R36") (pin "2") (pinfunction "2_2") (pintype "passive"))
    )
    (net (code "55") (name "Net-(D8-PadC)") (class "Default")
      (node (ref "D8") (pin "C") (pinfunction "C_C") (pintype "passive"))
      (node (ref "R37") (pin "2") (pinfunction "2_2") (pintype "passive"))
    )
    (net (code "56") (name "Net-(D9-PadC)") (class "Default")
      (node (ref "D9") (pin "C") (pinfunction "C_C") (pintype "passive"))
      (node (ref "R38") (pin "2") (pinfunction "2_2") (pintype "passive"))
    )
    (net (code "57") (name "Net-(D10-PadC)") (class "Default")
      (node (ref "D10") (pin "C") (pinfunction "C_C") (pintype "passive"))
      (node (ref "R39") (pin "2") (pinfunction "2_2") (pintype "passive"))
    )
    (net (code "58") (name "Net-(D11-PadC)") (class "Default")
      (node (ref "D11") (pin "C") (pinfunction "C_C") (pintype "passive"))
      (node (ref "D12") (pin "C") (pinfunction "C_C") (pintype "passive"))
      (node (ref "R25") (pin "2") (pinfunction "2_2") (pintype "passive"))
    )
    (net (code "59") (name "Net-(IC1A-+IN)") (class "Default")
      (node (ref "IC1") (pin "5") (pinfunction "+IN_5") (pintype "input"))
      (node (ref "R13") (pin "2") (pinfunction "2_2") (pintype "passive"))
      (node (ref "R17") (pin "1") (pinfunction "1_1") (pintype "passive"))
    )
    (net (code "60") (name "Net-(IC1A--IN)") (class "Default")
      (node (ref "IC1") (pin "10") (pinfunction "-IN_10") (pintype "input"))
      (node (ref "IC1") (pin "4") (pinfunction "-IN_4") (pintype "input"))
      (node (ref "IC1") (pin "6") (pinfunction "-IN_6") (pintype "input"))
      (node (ref "IC1") (pin "8") (pinfunction "-IN_8") (pintype "input"))
      (node (ref "R11") (pin "2") (pinfunction "2_2") (pintype "passive"))
      (node (ref "R12") (pin "2") (pinfunction "2_2") (pintype "passive"))
    )
    (net (code "61") (name "Net-(IC1B-+IN)") (class "Default")
      (node (ref "IC1") (pin "7") (pinfunction "+IN_7") (pintype "input"))
      (node (ref "R14") (pin "2") (pinfunction "2_2") (pintype "passive"))
      (node (ref "R18") (pin "1") (pinfunction "1_1") (pintype "passive"))
    )
    (net (code "62") (name "Net-(IC1C-+IN)") (class "Default")
      (node (ref "IC1") (pin "9") (pinfunction "+IN_9") (pintype "input"))
      (node (ref "R15") (pin "2") (pinfunction "2_2") (pintype "passive"))
      (node (ref "R19") (pin "1") (pinfunction "1_1") (pintype "passive"))
    )
    (net (code "63") (name "Net-(IC1D-+IN)") (class "Default")
      (node (ref "IC1") (pin "11") (pinfunction "+IN_11") (pintype "input"))
      (node (ref "R16") (pin "2") (pinfunction "2_2") (pintype "passive"))
      (node (ref "R20") (pin "1") (pinfunction "1_1") (pintype "passive"))
    )
    (net (code "64") (name "Net-(IC2A-CLK)") (class "Default")
      (node (ref "C10") (pin "1") (pinfunction "1_1") (pintype "passive"))
      (node (ref "IC2") (pin "15") (pinfunction "CLK_15") (pintype "input"))
      (node (ref "R25") (pin "1") (pinfunction "1_1") (pintype "passive"))
      (node (ref "R26") (pin "2") (pinfunction "2_2") (pintype "passive"))
    )
    (net (code "65") (name "Net-(IC2A-Q0)") (class "Default")
      (node (ref "IC2") (pin "6") (pinfunction "Q0_6") (pintype "output"))
      (node (ref "IC3") (pin "1") (pinfunction "A0_1") (pintype "input"))
      (node (ref "IC4") (pin "1") (pinfunction "A0_1") (pintype "input"))
      (node (ref "IC5") (pin "10") (pinfunction "A_10") (pintype "input"))
    )
    (net (code "66") (name "Net-(IC2A-Q1)") (class "Default")
      (node (ref "IC2") (pin "11") (pinfunction "Q1_11") (pintype "output"))
      (node (ref "IC3") (pin "16") (pinfunction "A1_16") (pintype "input"))
      (node (ref "IC4") (pin "16") (pinfunction "A1_16") (pintype "input"))
      (node (ref "IC5") (pin "9") (pinfunction "B_9") (pintype "input"))
    )
    (net (code "67") (name "Net-(IC3-DA)") (class "Default")
      (node (ref "IC3") (pin "8") (pinfunction "DA_8") (pintype "passive"))
      (node (ref "R31") (pin "1") (pinfunction "1_1") (pintype "passive"))
    )
    (net (code "68") (name "Net-(IC3-DB)") (class "Default")
      (node (ref "IC3") (pin "9") (pinfunction "DB_9") (pintype "passive"))
      (node (ref "R32") (pin "1") (pinfunction "1_1") (pintype "passive"))
    )
    (net (code "69") (name "Net-(IC3-GND)") (class "Default")
      (node (ref "IC3") (pin "15") (pinfunction "GND_15") (pintype "power_in"))
      (node (ref "IC4") (pin "15") (pinfunction "GND_15") (pintype "power_in"))
      (node (ref "SV6") (pin "5") (pinfunction "5_5") (pintype "passive"))
    )
    (net (code "70") (name "Net-(IC4-DA)") (class "Default")
      (node (ref "IC4") (pin "8") (pinfunction "DA_8") (pintype "passive"))
      (node (ref "R33") (pin "1") (pinfunction "1_1") (pintype "passive"))
    )
    (net (code "71") (name "Net-(IC4-DB)") (class "Default")
      (node (ref "IC4") (pin "9") (pinfunction "DB_9") (pintype "passive"))
      (node (ref "R34") (pin "1") (pinfunction "1_1") (pintype "passive"))
    )
    (net (code "72") (name "Net-(IC5A-X)") (class "Default")
      (node (ref "IC5") (pin "13") (pinfunction "X_13") (pintype "bidirectional"))
      (node (ref "R35") (pin "1") (pinfunction "1_1") (pintype "passive"))
    )
    (net (code "73") (name "Net-(L1-C)") (class "Default")
      (node (ref "L1") (pin "K") (pinfunction "C_K") (pintype "passive"))
      (node (ref "Q1") (pin "1") (pinfunction "D_1") (pintype "passive"))
    )
    (net (code "74") (name "Net-(L1-PadA)") (class "Default")
      (node (ref "L1") (pin "A") (pinfunction "A_A") (pintype "passive"))
      (node (ref "R3") (pin "1") (pinfunction "1_1") (pintype "passive"))
    )
    (net (code "75") (name "Net-(L2-C)") (class "Default")
      (node (ref "L2") (pin "K") (pinfunction "C_K") (pintype "passive"))
      (node (ref "Q2") (pin "1") (pinfunction "D_1") (pintype "passive"))
    )
    (net (code "76") (name "Net-(L2-PadA)") (class "Default")
      (node (ref "L2") (pin "A") (pinfunction "A_A") (pintype "passive"))
      (node (ref "R4") (pin "1") (pinfunction "1_1") (pintype "passive"))
    )
    (net (code "77") (name "Net-(L3-C)") (class "Default")
      (node (ref "L3") (pin "K") (pinfunction "C_K") (pintype "passive"))
      (node (ref "Q3") (pin "1") (pinfunction "D_1") (pintype "passive"))
    )
    (net (code "78") (name "Net-(L3-PadA)") (class "Default")
      (node (ref "L3") (pin "A") (pinfunction "A_A") (pintype "passive"))
      (node (ref "R5") (pin "1") (pinfunction "1_1") (pintype "passive"))
    )
    (net (code "79") (name "Net-(L4-C)") (class "Default")
      (node (ref "L4") (pin "K") (pinfunction "C_K") (pintype "passive"))
      (node (ref "Q4") (pin "1") (pinfunction "D_1") (pintype "passive"))
    )
    (net (code "80") (name "Net-(L4-PadA)") (class "Default")
      (node (ref "L4") (pin "A") (pinfunction "A_A") (pintype "passive"))
      (node (ref "R6") (pin "1") (pinfunction "1_1") (pintype "passive"))
    )
    (net (code "81") (name "Net-(POWER-Pad1)") (class "Default")
      (node (ref "POWER") (pin "1") (pinfunction "1_1") (pintype "passive"))
      (node (ref "POWER") (pin "2") (pinfunction "2_2") (pintype "passive"))
      (node (ref "R2") (pin "1") (pinfunction "1_1") (pintype "passive"))
    )
    (net (code "82") (name "Net-(POWER-Pad10)") (class "Default")
      (node (ref "POWER") (pin "10") (pinfunction "10_10") (pintype "passive"))
      (node (ref "POWER") (pin "9") (pinfunction "9_9") (pintype "passive"))
      (node (ref "R1") (pin "1") (pinfunction "1_1") (pintype "passive"))
    )
    (net (code "83") (name "unconnected-(FWD-SHUNT-PadNORMAL)") (class "Default")
      (node (ref "FWD") (pin "NORMAL") (pinfunction "SHUNT_NORMAL") (pintype "bidirectional"))
    )
    (net (code "84") (name "unconnected-(HLD-SHUNT-PadNORMAL)") (class "Default")
      (node (ref "HLD") (pin "NORMAL") (pinfunction "SHUNT_NORMAL") (pintype "bidirectional"))
    )
    (net (code "85") (name "unconnected-(I/O1-SHUNT-PadNORMAL)") (class "Default")
      (node (ref "I/O1") (pin "NORMAL") (pinfunction "SHUNT_NORMAL") (pintype "bidirectional"))
    )
    (net (code "86") (name "unconnected-(I/O2-SHUNT-PadNORMAL)") (class "Default")
      (node (ref "I/O2") (pin "NORMAL") (pinfunction "SHUNT_NORMAL") (pintype "bidirectional"))
    )
    (net (code "87") (name "unconnected-(I/O3-SHUNT-PadNORMAL)") (class "Default")
      (node (ref "I/O3") (pin "NORMAL") (pinfunction "SHUNT_NORMAL") (pintype "bidirectional"))
    )
    (net (code "88") (name "unconnected-(I/O4-SHUNT-PadNORMAL)") (class "Default")
      (node (ref "I/O4") (pin "NORMAL") (pinfunction "SHUNT_NORMAL") (pintype "bidirectional"))
    )
    (net (code "89") (name "unconnected-(IC2A-CO-Pad7)") (class "Default")
      (node (ref "IC2") (pin "7") (pinfunction "CO_7") (pintype "output"))
    )
    (net (code "90") (name "unconnected-(IC2A-Q2-Pad14)") (class "Default")
      (node (ref "IC2") (pin "14") (pinfunction "Q2_14") (pintype "output"))
    )
    (net (code "91") (name "unconnected-(IC2A-Q3-Pad2)") (class "Default")
      (node (ref "IC2") (pin "2") (pinfunction "Q3_2") (pintype "output"))
    )
    (net (code "92") (name "unconnected-(IC5A-Y0-Pad1)") (class "Default")
      (node (ref "IC5") (pin "1") (pinfunction "Y0_1") (pintype "bidirectional"))
    )
    (net (code "93") (name "unconnected-(IC5A-Y1-Pad5)") (class "Default")
      (node (ref "IC5") (pin "5") (pinfunction "Y1_5") (pintype "bidirectional"))
    )
    (net (code "94") (name "unconnected-(IC5A-Y2-Pad2)") (class "Default")
      (node (ref "IC5") (pin "2") (pinfunction "Y2_2") (pintype "bidirectional"))
    )
    (net (code "95") (name "unconnected-(IC5A-Y3-Pad4)") (class "Default")
      (node (ref "IC5") (pin "4") (pinfunction "Y3_4") (pintype "bidirectional"))
    )
    (net (code "96") (name "unconnected-(O/I1-SHUNT-PadNORMAL)") (class "Default")
      (node (ref "O/I1") (pin "NORMAL") (pinfunction "SHUNT_NORMAL") (pintype "bidirectional"))
    )
    (net (code "97") (name "unconnected-(O/I2-SHUNT-PadNORMAL)") (class "Default")
      (node (ref "O/I2") (pin "NORMAL") (pinfunction "SHUNT_NORMAL") (pintype "bidirectional"))
    )
    (net (code "98") (name "unconnected-(O/I3-SHUNT-PadNORMAL)") (class "Default")
      (node (ref "O/I3") (pin "NORMAL") (pinfunction "SHUNT_NORMAL") (pintype "bidirectional"))
    )
    (net (code "99") (name "unconnected-(O/I4-SHUNT-PadNORMAL)") (class "Default")
      (node (ref "O/I4") (pin "NORMAL") (pinfunction "SHUNT_NORMAL") (pintype "bidirectional"))
    )
    (net (code "100") (name "unconnected-(RES-SHUNT-PadNORMAL)") (class "Default")
      (node (ref "RES") (pin "NORMAL") (pinfunction "SHUNT_NORMAL") (pintype "bidirectional"))
    )
    (net (code "101") (name "unconnected-(REV-SHUNT-PadNORMAL)") (class "Default")
      (node (ref "REV") (pin "NORMAL") (pinfunction "SHUNT_NORMAL") (pintype "bidirectional"))
    )
  )
)
